# RFM300HEVB_V01.net
KiCad netlist of a schematic drawn in Altium Designer
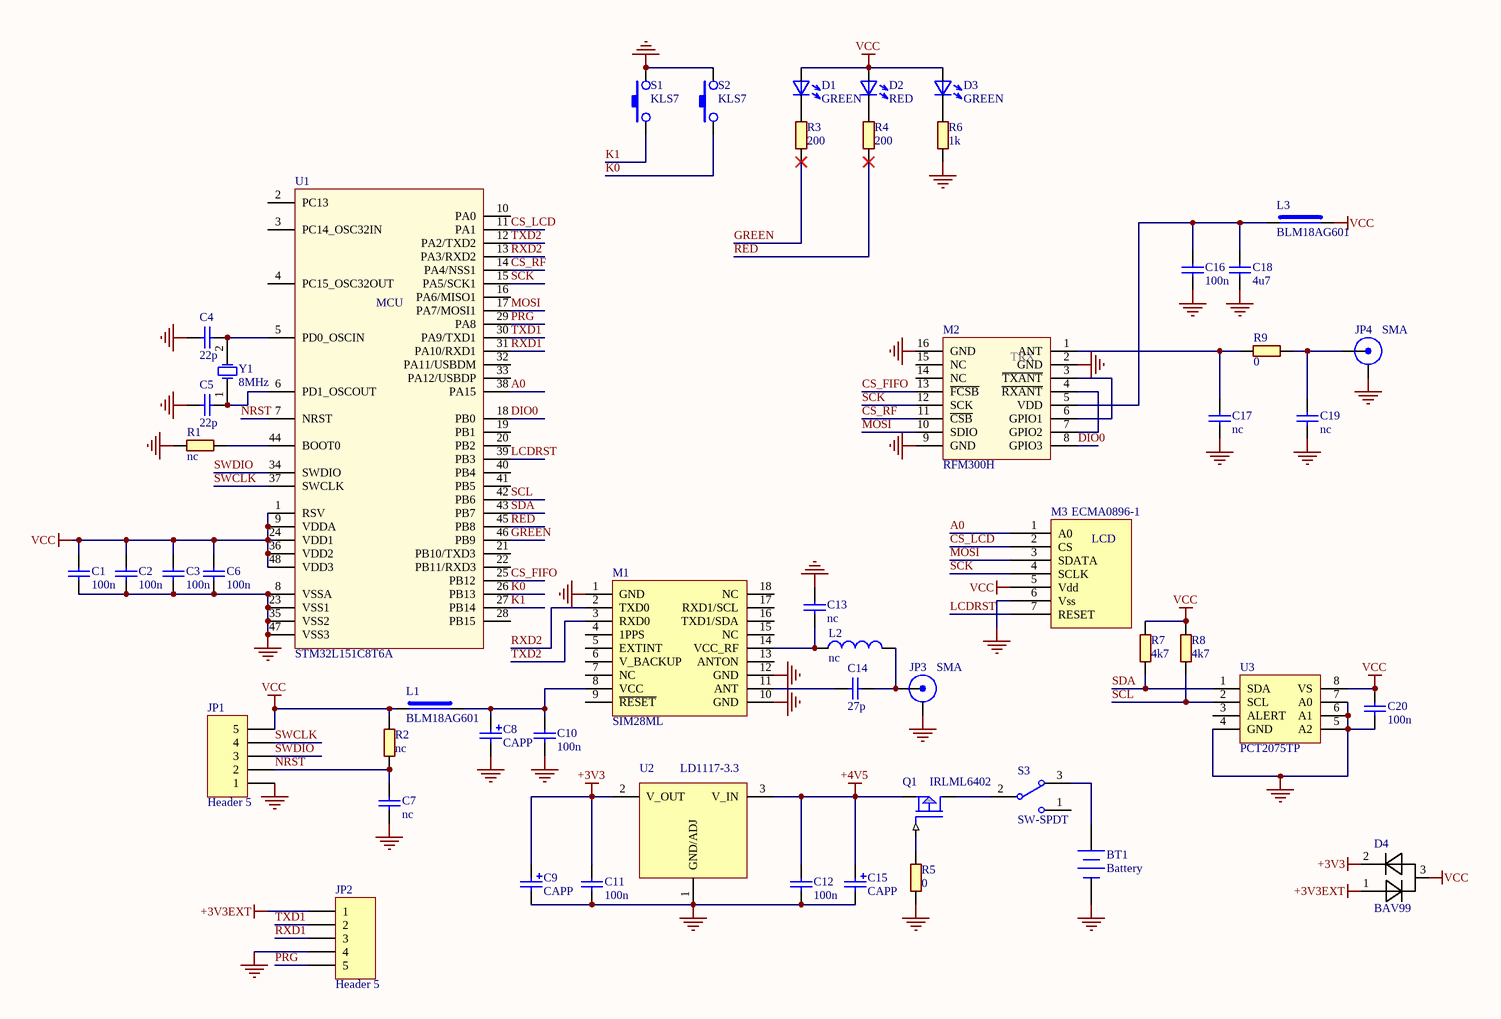
[diagram p0: RFM300HEVB_V01.SchDoc]

(export (version "E")
  (design (tool "Eeschema 10.0.6"))
  (components
    (comp (ref "BT1")
      (value "Battery")
      (footprint "3AAAHOLDER")
      (description "Multicell Battery")
      (fields (field (name "PUBLISHER") "Altium Limited"))
      (libsource (lib "Miscellaneous Devices") (part "Battery"))
    )
    (comp (ref "C1") (value "100n") (footprint "C-0603") (libsource (lib "Discrete") (part "CAPN")))
    (comp (ref "C2") (value "100n") (footprint "C-0603") (libsource (lib "Discrete") (part "CAPN")))
    (comp (ref "C3") (value "100n") (footprint "C-0603") (libsource (lib "Discrete") (part "CAPN")))
    (comp (ref "C4") (value "22p") (footprint "C-0603") (libsource (lib "Discrete") (part "CAPN")))
    (comp (ref "C5") (value "22p") (footprint "C-0603") (libsource (lib "Discrete") (part "CAPN")))
    (comp (ref "C6") (value "100n") (footprint "C-0603") (libsource (lib "Discrete") (part "CAPN")))
    (comp (ref "C7") (value "nc") (footprint "C-0603") (libsource (lib "Discrete") (part "CAPN")))
    (comp (ref "C8") (value "CAPP") (footprint "C-TANTAL-B") (libsource (lib "Discrete") (part "CAPP")))
    (comp (ref "C9") (value "CAPP") (footprint "C-TANTAL-B") (libsource (lib "Discrete") (part "CAPP")))
    (comp (ref "C10") (value "100n") (footprint "C-0603") (libsource (lib "Discrete") (part "CAPN")))
    (comp (ref "C11") (value "100n") (footprint "C-0603") (libsource (lib "Discrete") (part "CAPN")))
    (comp (ref "C12") (value "100n") (footprint "C-0603") (libsource (lib "Discrete") (part "CAPN")))
    (comp (ref "C13") (value "nc") (footprint "C-0603") (libsource (lib "Discrete") (part "CAPN")))
    (comp (ref "C14") (value "27p") (footprint "C-0603") (libsource (lib "Discrete") (part "CAPN")))
    (comp (ref "C15") (value "CAPP") (footprint "C-TANTAL-B") (libsource (lib "Discrete") (part "CAPP")))
    (comp (ref "C16") (value "100n") (footprint "C-0603") (libsource (lib "Discrete") (part "CAPN")))
    (comp (ref "C17") (value "nc") (footprint "C-0603") (libsource (lib "Discrete") (part "CAPN")))
    (comp (ref "C18") (value "4u7") (footprint "C-0805") (libsource (lib "Discrete") (part "CAPN")))
    (comp (ref "C19") (value "nc") (footprint "C-0603") (libsource (lib "Discrete") (part "CAPN")))
    (comp (ref "C20") (value "100n") (footprint "C-0603") (libsource (lib "Discrete") (part "CAPN")))
    (comp (ref "D1") (value "GREEN") (footprint "LED_0805") (libsource (lib "Discrete") (part "DLED")))
    (comp (ref "D2") (value "RED") (footprint "LED_0805") (libsource (lib "Discrete") (part "DLED")))
    (comp (ref "D3") (value "GREEN") (footprint "LED_0805") (libsource (lib "Discrete") (part "DLED")))
    (comp (ref "D4")
      (value "BAV99")
      (footprint "SOT23")
      (description "High-speed switching diodes 0.215 AMPERES, 100 VOLTS, Cjmax=2pF, SOT-23")
      (libsource (lib "Diodes") (part "BAV99"))
    )
    (comp (ref "JP1")
      (value "Header 5")
      (footprint "PLS1-5R")
      (description "Header, 5-Pin")
      (fields (field (name "PUBLISHER") "Altium Limited"))
      (libsource (lib "") (part "Header 5_1"))
    )
    (comp (ref "JP2")
      (value "Header 5")
      (footprint "PLS1-5R")
      (description "Header, 5-Pin")
      (fields (field (name "PUBLISHER") "Altium Limited"))
      (libsource (lib "Miscellaneous Connectors") (part "Header 5"))
    )
    (comp (ref "JP3")
      (value "SMA")
      (footprint "AMPHENOL_132357-11")
      (description "RF Connector")
      (libsource (lib "Connectors$switces") (part "X-004"))
    )
    (comp (ref "JP4")
      (value "SMA")
      (footprint "AMPHENOL_132357-11")
      (description "RF Connector")
      (libsource (lib "Connectors$switces") (part "X-004"))
    )
    (comp (ref "L1") (value "BLM18AG601") (footprint "L-0603") (libsource (lib "Discrete") (part "SUPRESOR")))
    (comp (ref "L2") (value "nc") (footprint "L-0603") (libsource (lib "Discrete") (part "L")))
    (comp (ref "L3") (value "BLM18AG601") (footprint "L-0603") (libsource (lib "Discrete") (part "SUPRESOR")))
    (comp (ref "M1")
      (value "SIM28ML")
      (footprint "LGA18_GNSS")
      (libsource (lib "Cellular_GNSS") (part "SIM28ML"))
    )
    (comp (ref "M2")
      (value "RFM300H")
      (footprint "LGA16C200P2X8_1600X1600X200")
      (libsource (lib "RFtest") (part "RFM300H"))
    )
    (comp (ref "M3") (value "ECMA0896-1") (footprint "PLS1-7") (libsource (lib "RCS-IMS") (part "ECMA0896")))
    (comp (ref "Q1") (value "IRLML6402") (footprint "SOT-23") (libsource (lib "Discrete") (part "IRLML6402")))
    (comp (ref "R1") (value "nc") (footprint "R-0603") (libsource (lib "") (part "RES_1")))
    (comp (ref "R2") (value "nc") (footprint "R-0603") (libsource (lib "") (part "RES_2")))
    (comp (ref "R3") (value "200") (footprint "R-0603") (libsource (lib "Discrete") (part "RES")))
    (comp (ref "R4") (value "200") (footprint "R-0603") (libsource (lib "Discrete") (part "RES")))
    (comp (ref "R5") (value "0") (footprint "R-0603") (libsource (lib "") (part "RES_2")))
    (comp (ref "R6") (value "1k") (footprint "R-0603") (libsource (lib "Discrete") (part "RES")))
    (comp (ref "R7") (value "4k7") (footprint "R-0603") (libsource (lib "") (part "RES_2")))
    (comp (ref "R8") (value "4k7") (footprint "R-0603") (libsource (lib "") (part "RES_2")))
    (comp (ref "R9") (value "0") (footprint "R-0603") (libsource (lib "") (part "RES_1")))
    (comp (ref "S1") (value "KLS7") (footprint "KLS7-TS3602") (libsource (lib "CLAP DM-WL-R2") (part "SW-1")))
    (comp (ref "S2") (value "KLS7") (footprint "KLS7-TS3602") (libsource (lib "CLAP DM-WL-R2") (part "SW-1")))
    (comp (ref "S3")
      (value "SW-SPDT")
      (footprint "SPDT_100mil")
      (description "SPDT Subminiature Toggle Switch, Right Angle Mounting, Vertical Actuation")
      (fields (field (name "PUBLISHER") "Altium Limited"))
      (libsource (lib "Miscellaneous Devices") (part "SW-SPDT"))
    )
    (comp (ref "U1")
      (value "STM32L151C8T6A")
      (footprint "LQFP-48")
      (libsource (lib "RFtest") (part "STM32L151C8T6"))
    )
    (comp (ref "U2")
      (value "LD1117-3.3")
      (footprint "SOT230P700X180-4N")
      (libsource (lib "SB") (part "LM1117_3.3"))
    )
    (comp (ref "U3") (value "PCT2075TP") (footprint "SOT1069-2") (libsource (lib "UL2016_v2") (part "TMP75")))
    (comp (ref "Y1")
      (value "8MHz")
      (footprint "HC49_3.5mm")
      (description "Crystal Oscillator")
      (fields (field (name "PUBLISHER") "Altium Limited"))
      (libsource (lib "Miscellaneous Devices") (part "XTAL"))
    )
  )
  (nets
    (net (code "1") (name "+3V3") (class "Default")
      (node (ref "C11") (pin "1") (pinfunction "1_1") (pintype "passive"))
      (node (ref "C9") (pin "2") (pinfunction "2_2") (pintype "passive"))
      (node (ref "D4") (pin "2") (pinfunction "2_2") (pintype "passive"))
      (node (ref "U2") (pin "2") (pinfunction "V_OUT_2") (pintype "passive"))
    )
    (net (code "2") (name "+3V3EXT") (class "Default")
      (node (ref "D4") (pin "1") (pinfunction "1_1") (pintype "passive"))
      (node (ref "JP2") (pin "1") (pinfunction "1_1") (pintype "passive"))
    )
    (net (code "3") (name "+4V5") (class "Default")
      (node (ref "C12") (pin "1") (pinfunction "1_1") (pintype "passive"))
      (node (ref "C15") (pin "2") (pinfunction "2_2") (pintype "passive"))
      (node (ref "Q1") (pin "2") (pinfunction "SOURCE_2") (pintype "passive"))
      (node (ref "U2") (pin "3") (pinfunction "V_IN_3") (pintype "passive"))
    )
    (net (code "4") (name "/A0") (class "Default")
      (node (ref "M3") (pin "1") (pinfunction "A0_1") (pintype "passive"))
      (node (ref "U1") (pin "38") (pinfunction "PA15_38") (pintype "passive"))
    )
    (net (code "5") (name "/CS_FIFO") (class "Default")
      (node (ref "M2") (pin "13") (pinfunction "~{FCSB}_13") (pintype "passive"))
      (node (ref "U1") (pin "25") (pinfunction "PB12_25") (pintype "passive"))
    )
    (net (code "6") (name "/CS_LCD") (class "Default")
      (node (ref "M3") (pin "2") (pinfunction "CS_2") (pintype "passive"))
      (node (ref "U1") (pin "11") (pinfunction "PA1_11") (pintype "passive"))
    )
    (net (code "7") (name "/CS_RF") (class "Default")
      (node (ref "M2") (pin "11") (pinfunction "~{CSB}_11") (pintype "passive"))
      (node (ref "U1") (pin "14") (pinfunction "PA4/NSS1_14") (pintype "passive"))
    )
    (net (code "8") (name "/DIO0") (class "Default")
      (node (ref "M2") (pin "8") (pinfunction "GPIO3_8") (pintype "passive"))
      (node (ref "U1") (pin "18") (pinfunction "PB0_18") (pintype "passive"))
    )
    (net (code "9") (name "/GREEN") (class "Default")
      (node (ref "R3") (pin "2") (pinfunction "2_2") (pintype "passive"))
      (node (ref "U1") (pin "46") (pinfunction "PB9_46") (pintype "passive"))
    )
    (net (code "10") (name "/K0") (class "Default")
      (node (ref "S2") (pin "1") (pinfunction "1_1") (pintype "passive"))
      (node (ref "U1") (pin "26") (pinfunction "PB13_26") (pintype "passive"))
    )
    (net (code "11") (name "/K1") (class "Default")
      (node (ref "S1") (pin "1") (pinfunction "1_1") (pintype "passive"))
      (node (ref "U1") (pin "27") (pinfunction "PB14_27") (pintype "passive"))
    )
    (net (code "12") (name "/LCDRST") (class "Default")
      (node (ref "M3") (pin "7") (pinfunction "RESET_7") (pintype "passive"))
      (node (ref "U1") (pin "39") (pinfunction "PB3_39") (pintype "passive"))
    )
    (net (code "13") (name "/MOSI") (class "Default")
      (node (ref "M2") (pin "10") (pinfunction "SDIO_10") (pintype "passive"))
      (node (ref "M3") (pin "3") (pinfunction "SDATA_3") (pintype "passive"))
      (node (ref "U1") (pin "17") (pinfunction "PA7/MOSI1_17") (pintype "passive"))
    )
    (net (code "14") (name "/NRST") (class "Default")
      (node (ref "C7") (pin "1") (pinfunction "1_1") (pintype "passive"))
      (node (ref "JP1") (pin "2") (pinfunction "2_2") (pintype "passive"))
      (node (ref "R2") (pin "1") (pinfunction "1_1") (pintype "passive"))
      (node (ref "U1") (pin "7") (pinfunction "NRST_7") (pintype "passive"))
    )
    (net (code "15") (name "/PRG") (class "Default")
      (node (ref "JP2") (pin "5") (pinfunction "5_5") (pintype "passive"))
      (node (ref "U1") (pin "29") (pinfunction "PA8_29") (pintype "passive"))
    )
    (net (code "16") (name "/RED") (class "Default")
      (node (ref "R4") (pin "2") (pinfunction "2_2") (pintype "passive"))
      (node (ref "U1") (pin "45") (pinfunction "PB8_45") (pintype "passive"))
    )
    (net (code "17") (name "/RXD1") (class "Default")
      (node (ref "JP2") (pin "3") (pinfunction "3_3") (pintype "passive"))
      (node (ref "U1") (pin "31") (pinfunction "PA10/RXD1_31") (pintype "passive"))
    )
    (net (code "18") (name "/RXD2") (class "Default")
      (node (ref "M1") (pin "2") (pinfunction "TXD0_2") (pintype "passive"))
      (node (ref "U1") (pin "13") (pinfunction "PA3/RXD2_13") (pintype "passive"))
    )
    (net (code "19") (name "/SCK") (class "Default")
      (node (ref "M2") (pin "12") (pinfunction "SCK_12") (pintype "passive"))
      (node (ref "M3") (pin "4") (pinfunction "SCLK_4") (pintype "passive"))
      (node (ref "U1") (pin "15") (pinfunction "PA5/SCK1_15") (pintype "passive"))
    )
    (net (code "20") (name "/SCL") (class "Default")
      (node (ref "R8") (pin "1") (pinfunction "1_1") (pintype "passive"))
      (node (ref "U1") (pin "42") (pinfunction "PB6_42") (pintype "passive"))
      (node (ref "U3") (pin "2") (pinfunction "SCL_2") (pintype "passive"))
    )
    (net (code "21") (name "/SDA") (class "Default")
      (node (ref "R7") (pin "1") (pinfunction "1_1") (pintype "passive"))
      (node (ref "U1") (pin "43") (pinfunction "PB7_43") (pintype "passive"))
      (node (ref "U3") (pin "1") (pinfunction "SDA_1") (pintype "passive"))
    )
    (net (code "22") (name "/SWCLK") (class "Default")
      (node (ref "JP1") (pin "4") (pinfunction "4_4") (pintype "passive"))
      (node (ref "U1") (pin "37") (pinfunction "SWCLK_37") (pintype "passive"))
    )
    (net (code "23") (name "/SWDIO") (class "Default")
      (node (ref "JP1") (pin "3") (pinfunction "3_3") (pintype "passive"))
      (node (ref "U1") (pin "34") (pinfunction "SWDIO_34") (pintype "passive"))
    )
    (net (code "24") (name "/TXD1") (class "Default")
      (node (ref "JP2") (pin "2") (pinfunction "2_2") (pintype "passive"))
      (node (ref "U1") (pin "30") (pinfunction "PA9/TXD1_30") (pintype "passive"))
    )
    (net (code "25") (name "/TXD2") (class "Default")
      (node (ref "M1") (pin "3") (pinfunction "RXD0_3") (pintype "passive"))
      (node (ref "U1") (pin "12") (pinfunction "PA2/TXD2_12") (pintype "passive"))
    )
    (net (code "26") (name "GND") (class "Default")
      (node (ref "BT1") (pin "2") (pinfunction "-_2") (pintype "passive"))
      (node (ref "C1") (pin "2") (pinfunction "2_2") (pintype "passive"))
      (node (ref "C10") (pin "2") (pinfunction "2_2") (pintype "passive"))
      (node (ref "C11") (pin "2") (pinfunction "2_2") (pintype "passive"))
      (node (ref "C12") (pin "2") (pinfunction "2_2") (pintype "passive"))
      (node (ref "C13") (pin "1") (pinfunction "1_1") (pintype "passive"))
      (node (ref "C15") (pin "1") (pinfunction "1_1") (pintype "passive"))
      (node (ref "C16") (pin "2") (pinfunction "2_2") (pintype "passive"))
      (node (ref "C17") (pin "2") (pinfunction "2_2") (pintype "passive"))
      (node (ref "C18") (pin "2") (pinfunction "2_2") (pintype "passive"))
      (node (ref "C19") (pin "2") (pinfunction "2_2") (pintype "passive"))
      (node (ref "C2") (pin "2") (pinfunction "2_2") (pintype "passive"))
      (node (ref "C20") (pin "2") (pinfunction "2_2") (pintype "passive"))
      (node (ref "C3") (pin "2") (pinfunction "2_2") (pintype "passive"))
      (node (ref "C4") (pin "1") (pinfunction "1_1") (pintype "passive"))
      (node (ref "C5") (pin "1") (pinfunction "1_1") (pintype "passive"))
      (node (ref "C6") (pin "2") (pinfunction "2_2") (pintype "passive"))
      (node (ref "C7") (pin "2") (pinfunction "2_2") (pintype "passive"))
      (node (ref "C8") (pin "1") (pinfunction "1_1") (pintype "passive"))
      (node (ref "C9") (pin "1") (pinfunction "1_1") (pintype "passive"))
      (node (ref "JP1") (pin "1") (pinfunction "1_1") (pintype "passive"))
      (node (ref "JP2") (pin "4") (pinfunction "4_4") (pintype "passive"))
      (node (ref "JP3") (pin "2") (pinfunction "Y_2") (pintype "passive"))
      (node (ref "JP4") (pin "2") (pinfunction "Y_2") (pintype "passive"))
      (node (ref "M1") (pin "1") (pinfunction "GND_1") (pintype "passive"))
      (node (ref "M1") (pin "10") (pinfunction "GND_10") (pintype "passive"))
      (node (ref "M1") (pin "12") (pinfunction "GND_12") (pintype "passive"))
      (node (ref "M2") (pin "16") (pinfunction "GND_16") (pintype "passive"))
      (node (ref "M2") (pin "2") (pinfunction "GND_2") (pintype "passive"))
      (node (ref "M2") (pin "9") (pinfunction "GND_9") (pintype "passive"))
      (node (ref "M3") (pin "6") (pinfunction "Vss_6") (pintype "passive"))
      (node (ref "R1") (pin "1") (pinfunction "1_1") (pintype "passive"))
      (node (ref "R5") (pin "1") (pinfunction "1_1") (pintype "passive"))
      (node (ref "R6") (pin "2") (pinfunction "2_2") (pintype "passive"))
      (node (ref "S1") (pin "2") (pinfunction "2_2") (pintype "passive"))
      (node (ref "S2") (pin "2") (pinfunction "2_2") (pintype "passive"))
      (node (ref "U1") (pin "23") (pinfunction "VSS1_23") (pintype "passive"))
      (node (ref "U1") (pin "35") (pinfunction "VSS2_35") (pintype "passive"))
      (node (ref "U1") (pin "47") (pinfunction "VSS3_47") (pintype "passive"))
      (node (ref "U1") (pin "8") (pinfunction "VSSA_8") (pintype "passive"))
      (node (ref "U2") (pin "1") (pinfunction "GND/ADJ_1") (pintype "passive"))
      (node (ref "U3") (pin "4") (pinfunction "GND_4") (pintype "passive"))
      (node (ref "U3") (pin "5") (pinfunction "A2_5") (pintype "passive"))
      (node (ref "U3") (pin "6") (pinfunction "A1_6") (pintype "passive"))
      (node (ref "U3") (pin "7") (pinfunction "A0_7") (pintype "passive"))
    )
    (net (code "27") (name "Net-(BT1-+)") (class "Default")
      (node (ref "BT1") (pin "1") (pinfunction "+_1") (pintype "passive"))
      (node (ref "S3") (pin "3") (pinfunction "3_3") (pintype "passive"))
    )
    (net (code "28") (name "Net-(D1-2)") (class "Default")
      (node (ref "D1") (pin "K") (pinfunction "2_K") (pintype "passive"))
      (node (ref "R3") (pin "1") (pinfunction "1_1") (pintype "passive"))
    )
    (net (code "29") (name "Net-(D2-2)") (class "Default")
      (node (ref "D2") (pin "K") (pinfunction "2_K") (pintype "passive"))
      (node (ref "R4") (pin "1") (pinfunction "1_1") (pintype "passive"))
    )
    (net (code "30") (name "Net-(D3-2)") (class "Default")
      (node (ref "D3") (pin "K") (pinfunction "2_K") (pintype "passive"))
      (node (ref "R6") (pin "1") (pinfunction "1_1") (pintype "passive"))
    )
    (net (code "31") (name "Net-(JP3-X)") (class "Default")
      (node (ref "C14") (pin "2") (pinfunction "2_2") (pintype "passive"))
      (node (ref "JP3") (pin "1") (pinfunction "X_1") (pintype "passive"))
      (node (ref "L2") (pin "2") (pinfunction "2_2") (pintype "passive"))
    )
    (net (code "32") (name "Net-(JP4-X)") (class "Default")
      (node (ref "C19") (pin "1") (pinfunction "1_1") (pintype "passive"))
      (node (ref "JP4") (pin "1") (pinfunction "X_1") (pintype "passive"))
      (node (ref "R9") (pin "2") (pinfunction "2_2") (pintype "passive"))
    )
    (net (code "33") (name "Net-(M1-ANT)") (class "Default")
      (node (ref "C14") (pin "1") (pinfunction "1_1") (pintype "passive"))
      (node (ref "M1") (pin "11") (pinfunction "ANT_11") (pintype "passive"))
    )
    (net (code "34") (name "Net-(M1-VCC)") (class "Default")
      (node (ref "C10") (pin "1") (pinfunction "1_1") (pintype "passive"))
      (node (ref "C8") (pin "2") (pinfunction "2_2") (pintype "passive"))
      (node (ref "L1") (pin "2") (pinfunction "2_2") (pintype "passive"))
      (node (ref "M1") (pin "8") (pinfunction "VCC_8") (pintype "passive"))
    )
    (net (code "35") (name "Net-(M1-VCC_RF)") (class "Default")
      (node (ref "C13") (pin "2") (pinfunction "2_2") (pintype "passive"))
      (node (ref "L2") (pin "1") (pinfunction "1_1") (pintype "passive"))
      (node (ref "M1") (pin "14") (pinfunction "VCC_RF_14") (pintype "passive"))
    )
    (net (code "36") (name "Net-(M2-ANT)") (class "Default")
      (node (ref "C17") (pin "1") (pinfunction "1_1") (pintype "passive"))
      (node (ref "M2") (pin "1") (pinfunction "ANT_1") (pintype "passive"))
      (node (ref "R9") (pin "1") (pinfunction "1_1") (pintype "passive"))
    )
    (net (code "37") (name "Net-(M2-GPIO1)") (class "Default")
      (node (ref "M2") (pin "3") (pinfunction "~{TXANT}_3") (pintype "passive"))
      (node (ref "M2") (pin "6") (pinfunction "GPIO1_6") (pintype "passive"))
    )
    (net (code "38") (name "Net-(M2-GPIO2)") (class "Default")
      (node (ref "M2") (pin "4") (pinfunction "~{RXANT}_4") (pintype "passive"))
      (node (ref "M2") (pin "7") (pinfunction "GPIO2_7") (pintype "passive"))
    )
    (net (code "39") (name "Net-(M2-VDD)") (class "Default")
      (node (ref "C16") (pin "1") (pinfunction "1_1") (pintype "passive"))
      (node (ref "C18") (pin "1") (pinfunction "1_1") (pintype "passive"))
      (node (ref "L3") (pin "2") (pinfunction "2_2") (pintype "passive"))
      (node (ref "M2") (pin "5") (pinfunction "VDD_5") (pintype "passive"))
    )
    (net (code "40") (name "Net-(Q1-DRAIN)") (class "Default")
      (node (ref "Q1") (pin "3") (pinfunction "DRAIN_3") (pintype "passive"))
      (node (ref "S3") (pin "2") (pinfunction "2_2") (pintype "passive"))
    )
    (net (code "41") (name "Net-(Q1-GATE)") (class "Default")
      (node (ref "Q1") (pin "1") (pinfunction "GATE_1") (pintype "input"))
      (node (ref "R5") (pin "2") (pinfunction "2_2") (pintype "passive"))
    )
    (net (code "42") (name "Net-(U1-BOOT0)") (class "Default")
      (node (ref "R1") (pin "2") (pinfunction "2_2") (pintype "passive"))
      (node (ref "U1") (pin "44") (pinfunction "BOOT0_44") (pintype "passive"))
    )
    (net (code "43") (name "Net-(U1-PD0_OSCIN)") (class "Default")
      (node (ref "C4") (pin "2") (pinfunction "2_2") (pintype "passive"))
      (node (ref "U1") (pin "5") (pinfunction "PD0_OSCIN_5") (pintype "passive"))
      (node (ref "Y1") (pin "2") (pinfunction "OSC2_2") (pintype "passive"))
    )
    (net (code "44") (name "Net-(U1-PD1_OSCOUT)") (class "Default")
      (node (ref "C5") (pin "2") (pinfunction "2_2") (pintype "passive"))
      (node (ref "U1") (pin "6") (pinfunction "PD1_OSCOUT_6") (pintype "passive"))
      (node (ref "Y1") (pin "1") (pinfunction "OSC1_1") (pintype "passive"))
    )
    (net (code "45") (name "VCC") (class "Default")
      (node (ref "C1") (pin "1") (pinfunction "1_1") (pintype "passive"))
      (node (ref "C2") (pin "1") (pinfunction "1_1") (pintype "passive"))
      (node (ref "C20") (pin "1") (pinfunction "1_1") (pintype "passive"))
      (node (ref "C3") (pin "1") (pinfunction "1_1") (pintype "passive"))
      (node (ref "C6") (pin "1") (pinfunction "1_1") (pintype "passive"))
      (node (ref "D1") (pin "A") (pinfunction "1_A") (pintype "passive"))
      (node (ref "D2") (pin "A") (pinfunction "1_A") (pintype "passive"))
      (node (ref "D3") (pin "A") (pinfunction "1_A") (pintype "passive"))
      (node (ref "D4") (pin "3") (pinfunction "3_3") (pintype "passive"))
      (node (ref "JP1") (pin "5") (pinfunction "5_5") (pintype "passive"))
      (node (ref "L1") (pin "1") (pinfunction "1_1") (pintype "passive"))
      (node (ref "L3") (pin "1") (pinfunction "1_1") (pintype "passive"))
      (node (ref "M3") (pin "5") (pinfunction "Vdd_5") (pintype "passive"))
      (node (ref "R2") (pin "2") (pinfunction "2_2") (pintype "passive"))
      (node (ref "R7") (pin "2") (pinfunction "2_2") (pintype "passive"))
      (node (ref "R8") (pin "2") (pinfunction "2_2") (pintype "passive"))
      (node (ref "U1") (pin "1") (pinfunction "RSV_1") (pintype "passive"))
      (node (ref "U1") (pin "24") (pinfunction "VDD1_24") (pintype "passive"))
      (node (ref "U1") (pin "36") (pinfunction "VDD2_36") (pintype "passive"))
      (node (ref "U1") (pin "48") (pinfunction "VDD3_48") (pintype "passive"))
      (node (ref "U1") (pin "9") (pinfunction "VDDA_9") (pintype "passive"))
      (node (ref "U3") (pin "8") (pinfunction "VS_8") (pintype "passive"))
    )
    (net (code "46") (name "unconnected-(M1-1PPS-Pad4)") (class "Default")
      (node (ref "M1") (pin "4") (pinfunction "1PPS_4") (pintype "passive"))
    )
    (net (code "47") (name "unconnected-(M1-ANTON-Pad13)") (class "Default")
      (node (ref "M1") (pin "13") (pinfunction "ANTON_13") (pintype "passive"))
    )
    (net (code "48") (name "unconnected-(M1-EXTINT-Pad5)") (class "Default")
      (node (ref "M1") (pin "5") (pinfunction "EXTINT_5") (pintype "passive"))
    )
    (net (code "49") (name "unconnected-(M1-NC-Pad7)") (class "Default")
      (node (ref "M1") (pin "7") (pinfunction "NC_7") (pintype "passive"))
    )
    (net (code "50") (name "unconnected-(M1-NC-Pad15)") (class "Default")
      (node (ref "M1") (pin "15") (pinfunction "NC_15") (pintype "passive"))
    )
    (net (code "51") (name "unconnected-(M1-NC-Pad18)") (class "Default")
      (node (ref "M1") (pin "18") (pinfunction "NC_18") (pintype "passive"))
    )
    (net (code "52") (name "unconnected-(M1-RXD1{slash}SCL-Pad17)") (class "Default")
      (node (ref "M1") (pin "17") (pinfunction "RXD1/SCL_17") (pintype "passive"))
    )
    (net (code "53") (name "unconnected-(M1-TXD1{slash}SDA-Pad16)") (class "Default")
      (node (ref "M1") (pin "16") (pinfunction "TXD1/SDA_16") (pintype "passive"))
    )
    (net (code "54") (name "unconnected-(M1-V_BACKUP-Pad6)") (class "Default")
      (node (ref "M1") (pin "6") (pinfunction "V_BACKUP_6") (pintype "passive"))
    )
    (net (code "55") (name "unconnected-(M1-~{RESET}-Pad9)") (class "Default")
      (node (ref "M1") (pin "9") (pinfunction "~{RESET}_9") (pintype "passive"))
    )
    (net (code "56") (name "unconnected-(M2-NC-Pad14)") (class "Default")
      (node (ref "M2") (pin "14") (pinfunction "NC_14") (pintype "passive"))
    )
    (net (code "57") (name "unconnected-(M2-NC-Pad15)") (class "Default")
      (node (ref "M2") (pin "15") (pinfunction "NC_15") (pintype "passive"))
    )
    (net (code "58") (name "unconnected-(S3-Pad1)") (class "Default")
      (node (ref "S3") (pin "1") (pinfunction "1_1") (pintype "passive"))
    )
    (net (code "59") (name "unconnected-(U1-PA0-Pad10)") (class "Default")
      (node (ref "U1") (pin "10") (pinfunction "PA0_10") (pintype "passive"))
    )
    (net (code "60") (name "unconnected-(U1-PA6{slash}MISO1-Pad16)") (class "Default")
      (node (ref "U1") (pin "16") (pinfunction "PA6/MISO1_16") (pintype "passive"))
    )
    (net (code "61") (name "unconnected-(U1-PA11{slash}USBDM-Pad32)") (class "Default")
      (node (ref "U1") (pin "32") (pinfunction "PA11/USBDM_32") (pintype "passive"))
    )
    (net (code "62") (name "unconnected-(U1-PA12{slash}USBDP-Pad33)") (class "Default")
      (node (ref "U1") (pin "33") (pinfunction "PA12/USBDP_33") (pintype "passive"))
    )
    (net (code "63") (name "unconnected-(U1-PB1-Pad19)") (class "Default")
      (node (ref "U1") (pin "19") (pinfunction "PB1_19") (pintype "passive"))
    )
    (net (code "64") (name "unconnected-(U1-PB2-Pad20)") (class "Default")
      (node (ref "U1") (pin "20") (pinfunction "PB2_20") (pintype "passive"))
    )
    (net (code "65") (name "unconnected-(U1-PB4-Pad40)") (class "Default")
      (node (ref "U1") (pin "40") (pinfunction "PB4_40") (pintype "passive"))
    )
    (net (code "66") (name "unconnected-(U1-PB5-Pad41)") (class "Default")
      (node (ref "U1") (pin "41") (pinfunction "PB5_41") (pintype "passive"))
    )
    (net (code "67") (name "unconnected-(U1-PB10{slash}TXD3-Pad21)") (class "Default")
      (node (ref "U1") (pin "21") (pinfunction "PB10/TXD3_21") (pintype "passive"))
    )
    (net (code "68") (name "unconnected-(U1-PB11{slash}RXD3-Pad22)") (class "Default")
      (node (ref "U1") (pin "22") (pinfunction "PB11/RXD3_22") (pintype "passive"))
    )
    (net (code "69") (name "unconnected-(U1-PB15-Pad28)") (class "Default")
      (node (ref "U1") (pin "28") (pinfunction "PB15_28") (pintype "passive"))
    )
    (net (code "70") (name "unconnected-(U1-PC13-Pad2)") (class "Default")
      (node (ref "U1") (pin "2") (pinfunction "PC13_2") (pintype "passive"))
    )
    (net (code "71") (name "unconnected-(U1-PC14_OSC32IN-Pad3)") (class "Default")
      (node (ref "U1") (pin "3") (pinfunction "PC14_OSC32IN_3") (pintype "passive"))
    )
    (net (code "72") (name "unconnected-(U1-PC15_OSC32OUT-Pad4)") (class "Default")
      (node (ref "U1") (pin "4") (pinfunction "PC15_OSC32OUT_4") (pintype "passive"))
    )
    (net (code "73") (name "unconnected-(U3-ALERT-Pad3)") (class "Default")
      (node (ref "U3") (pin "3") (pinfunction "ALERT_3") (pintype "passive"))
    )
  )
)
